# Shield.net
KiCad netlist of a schematic drawn in EAGLE
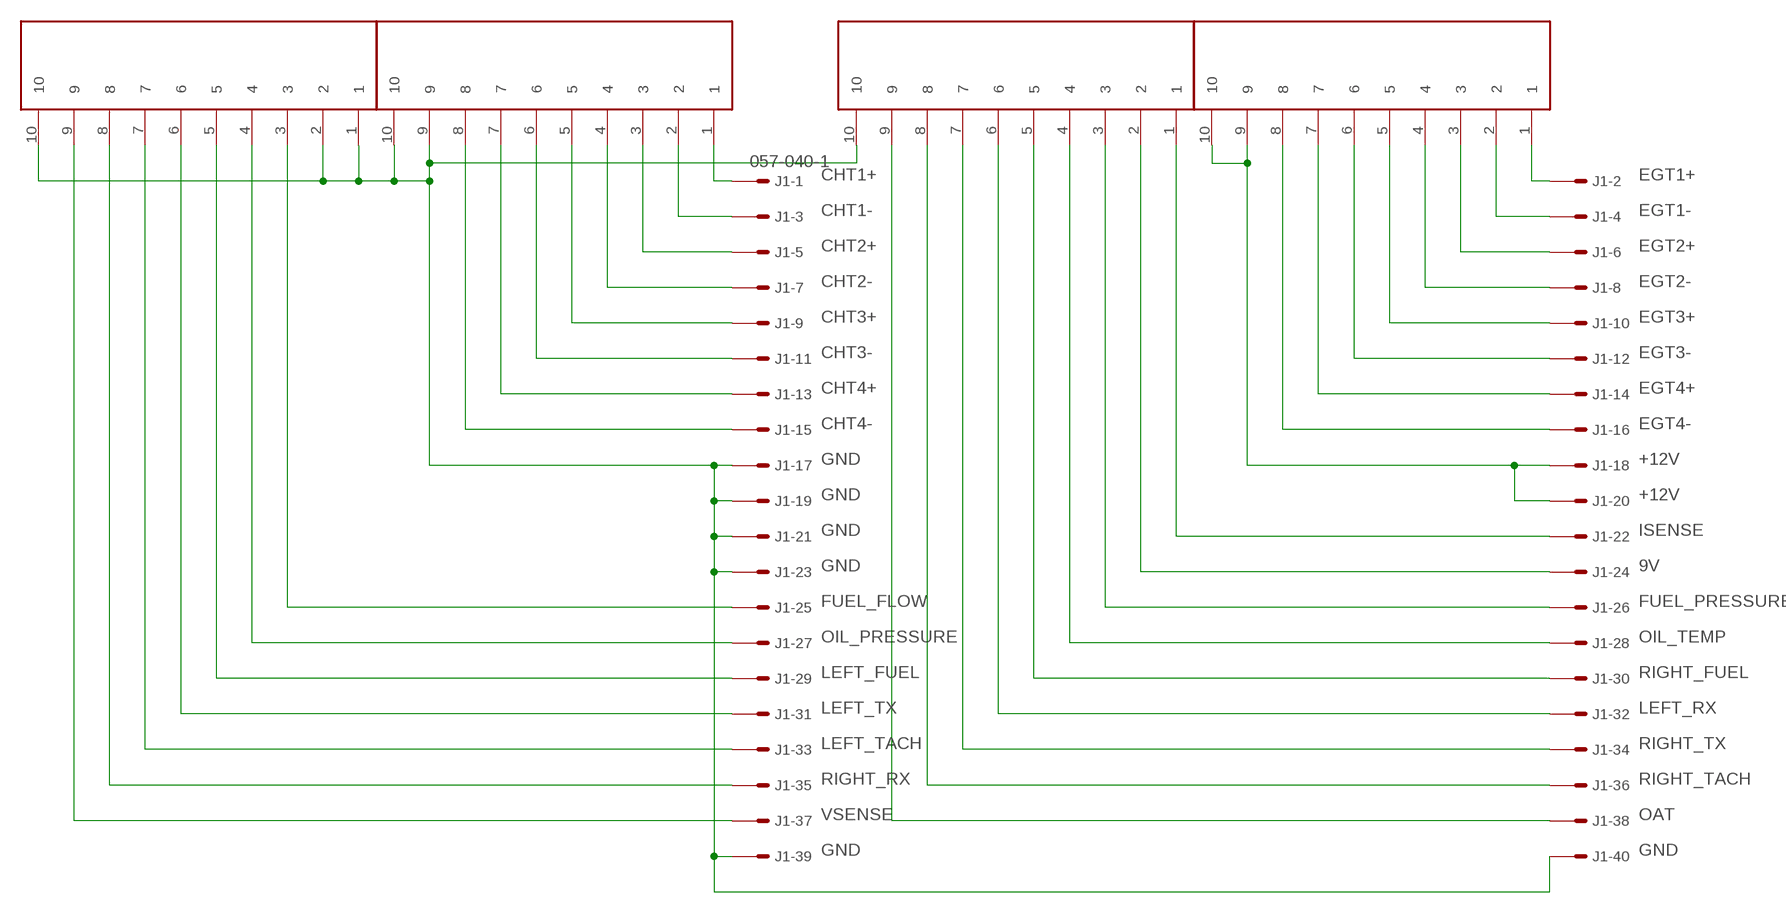
[diagram p0: schematic, sheet 1]

(export (version "E")
  (design (tool "Eeschema 10.0.6"))
  (components
    (comp (ref "J1")
      (value "057-040-1")
      (footprint "eagle-import:057-040-1")
      (fields (field (name "PARTNO") "SBH11-PBPC-D20-ST-BK"))
      (libsource (lib "eagle-import") (part "057-040-1"))
    )
    (comp (ref "TB1")
      (value "282847-10")
      (footprint "eagle-import:282847-10")
      (fields (field (name "PARTNO") "1-282847-0"))
      (libsource (lib "eagle-import") (part "282847-10"))
    )
    (comp (ref "TB2")
      (value "282847-10")
      (footprint "eagle-import:282847-10")
      (fields (field (name "PARTNO") "1-282847-0"))
      (libsource (lib "eagle-import") (part "282847-10"))
    )
    (comp (ref "TB3")
      (value "282847-10")
      (footprint "eagle-import:282847-10")
      (fields (field (name "PARTNO") "1-282847-0"))
      (libsource (lib "eagle-import") (part "282847-10"))
    )
    (comp (ref "TB4")
      (value "282847-10")
      (footprint "eagle-import:282847-10")
      (fields (field (name "PARTNO") "1-282847-0"))
      (libsource (lib "eagle-import") (part "282847-10"))
    )
  )
  (nets
    (net (code "1") (name "/+12V") (class "Default")
      (node (ref "J1") (pin "18") (pinfunction "S_18") (pintype "passive"))
      (node (ref "J1") (pin "20") (pinfunction "S_20") (pintype "passive"))
      (node (ref "TB4") (pin "10") (pinfunction "10_10") (pintype "bidirectional"))
      (node (ref "TB4") (pin "9") (pinfunction "9_9") (pintype "bidirectional"))
    )
    (net (code "2") (name "/9V") (class "Default")
      (node (ref "J1") (pin "24") (pinfunction "S_24") (pintype "passive"))
      (node (ref "TB3") (pin "2") (pinfunction "2_2") (pintype "bidirectional"))
    )
    (net (code "3") (name "/CHT1+") (class "Default")
      (node (ref "J1") (pin "1") (pinfunction "S_1") (pintype "passive"))
      (node (ref "TB2") (pin "1") (pinfunction "1_1") (pintype "bidirectional"))
    )
    (net (code "4") (name "/CHT1-") (class "Default")
      (node (ref "J1") (pin "3") (pinfunction "S_3") (pintype "passive"))
      (node (ref "TB2") (pin "2") (pinfunction "2_2") (pintype "bidirectional"))
    )
    (net (code "5") (name "/CHT2+") (class "Default")
      (node (ref "J1") (pin "5") (pinfunction "S_5") (pintype "passive"))
      (node (ref "TB2") (pin "3") (pinfunction "3_3") (pintype "bidirectional"))
    )
    (net (code "6") (name "/CHT2-") (class "Default")
      (node (ref "J1") (pin "7") (pinfunction "S_7") (pintype "passive"))
      (node (ref "TB2") (pin "4") (pinfunction "4_4") (pintype "bidirectional"))
    )
    (net (code "7") (name "/CHT3+") (class "Default")
      (node (ref "J1") (pin "9") (pinfunction "S_9") (pintype "passive"))
      (node (ref "TB2") (pin "5") (pinfunction "5_5") (pintype "bidirectional"))
    )
    (net (code "8") (name "/CHT3-") (class "Default")
      (node (ref "J1") (pin "11") (pinfunction "S_11") (pintype "passive"))
      (node (ref "TB2") (pin "6") (pinfunction "6_6") (pintype "bidirectional"))
    )
    (net (code "9") (name "/CHT4+") (class "Default")
      (node (ref "J1") (pin "13") (pinfunction "S_13") (pintype "passive"))
      (node (ref "TB2") (pin "7") (pinfunction "7_7") (pintype "bidirectional"))
    )
    (net (code "10") (name "/CHT4-") (class "Default")
      (node (ref "J1") (pin "15") (pinfunction "S_15") (pintype "passive"))
      (node (ref "TB2") (pin "8") (pinfunction "8_8") (pintype "bidirectional"))
    )
    (net (code "11") (name "/EGT1+") (class "Default")
      (node (ref "J1") (pin "2") (pinfunction "S_2") (pintype "passive"))
      (node (ref "TB4") (pin "1") (pinfunction "1_1") (pintype "bidirectional"))
    )
    (net (code "12") (name "/EGT1-") (class "Default")
      (node (ref "J1") (pin "4") (pinfunction "S_4") (pintype "passive"))
      (node (ref "TB4") (pin "2") (pinfunction "2_2") (pintype "bidirectional"))
    )
    (net (code "13") (name "/EGT2+") (class "Default")
      (node (ref "J1") (pin "6") (pinfunction "S_6") (pintype "passive"))
      (node (ref "TB4") (pin "3") (pinfunction "3_3") (pintype "bidirectional"))
    )
    (net (code "14") (name "/EGT2-") (class "Default")
      (node (ref "J1") (pin "8") (pinfunction "S_8") (pintype "passive"))
      (node (ref "TB4") (pin "4") (pinfunction "4_4") (pintype "bidirectional"))
    )
    (net (code "15") (name "/EGT3+") (class "Default")
      (node (ref "J1") (pin "10") (pinfunction "S_10") (pintype "passive"))
      (node (ref "TB4") (pin "5") (pinfunction "5_5") (pintype "bidirectional"))
    )
    (net (code "16") (name "/EGT3-") (class "Default")
      (node (ref "J1") (pin "12") (pinfunction "S_12") (pintype "passive"))
      (node (ref "TB4") (pin "6") (pinfunction "6_6") (pintype "bidirectional"))
    )
    (net (code "17") (name "/EGT4+") (class "Default")
      (node (ref "J1") (pin "14") (pinfunction "S_14") (pintype "passive"))
      (node (ref "TB4") (pin "7") (pinfunction "7_7") (pintype "bidirectional"))
    )
    (net (code "18") (name "/EGT4-") (class "Default")
      (node (ref "J1") (pin "16") (pinfunction "S_16") (pintype "passive"))
      (node (ref "TB4") (pin "8") (pinfunction "8_8") (pintype "bidirectional"))
    )
    (net (code "19") (name "/FUEL_FLOW") (class "Default")
      (node (ref "J1") (pin "25") (pinfunction "S_25") (pintype "passive"))
      (node (ref "TB1") (pin "3") (pinfunction "3_3") (pintype "bidirectional"))
    )
    (net (code "20") (name "/FUEL_PRESSURE") (class "Default")
      (node (ref "J1") (pin "26") (pinfunction "S_26") (pintype "passive"))
      (node (ref "TB3") (pin "3") (pinfunction "3_3") (pintype "bidirectional"))
    )
    (net (code "21") (name "/GND") (class "Default")
      (node (ref "J1") (pin "17") (pinfunction "S_17") (pintype "passive"))
      (node (ref "J1") (pin "19") (pinfunction "S_19") (pintype "passive"))
      (node (ref "J1") (pin "21") (pinfunction "S_21") (pintype "passive"))
      (node (ref "J1") (pin "23") (pinfunction "S_23") (pintype "passive"))
      (node (ref "J1") (pin "39") (pinfunction "S_39") (pintype "passive"))
      (node (ref "J1") (pin "40") (pinfunction "S_40") (pintype "passive"))
      (node (ref "TB1") (pin "1") (pinfunction "1_1") (pintype "bidirectional"))
      (node (ref "TB1") (pin "10") (pinfunction "10_10") (pintype "bidirectional"))
      (node (ref "TB1") (pin "2") (pinfunction "2_2") (pintype "bidirectional"))
      (node (ref "TB2") (pin "10") (pinfunction "10_10") (pintype "bidirectional"))
      (node (ref "TB2") (pin "9") (pinfunction "9_9") (pintype "bidirectional"))
      (node (ref "TB3") (pin "10") (pinfunction "10_10") (pintype "bidirectional"))
    )
    (net (code "22") (name "/ISENSE") (class "Default")
      (node (ref "J1") (pin "22") (pinfunction "S_22") (pintype "passive"))
      (node (ref "TB3") (pin "1") (pinfunction "1_1") (pintype "bidirectional"))
    )
    (net (code "23") (name "/LEFT_FUEL") (class "Default")
      (node (ref "J1") (pin "29") (pinfunction "S_29") (pintype "passive"))
      (node (ref "TB1") (pin "5") (pinfunction "5_5") (pintype "bidirectional"))
    )
    (net (code "24") (name "/LEFT_RX") (class "Default")
      (node (ref "J1") (pin "32") (pinfunction "S_32") (pintype "passive"))
      (node (ref "TB3") (pin "6") (pinfunction "6_6") (pintype "bidirectional"))
    )
    (net (code "25") (name "/LEFT_TACH") (class "Default")
      (node (ref "J1") (pin "33") (pinfunction "S_33") (pintype "passive"))
      (node (ref "TB1") (pin "7") (pinfunction "7_7") (pintype "bidirectional"))
    )
    (net (code "26") (name "/LEFT_TX") (class "Default")
      (node (ref "J1") (pin "31") (pinfunction "S_31") (pintype "passive"))
      (node (ref "TB1") (pin "6") (pinfunction "6_6") (pintype "bidirectional"))
    )
    (net (code "27") (name "/OAT") (class "Default")
      (node (ref "J1") (pin "38") (pinfunction "S_38") (pintype "passive"))
      (node (ref "TB3") (pin "9") (pinfunction "9_9") (pintype "bidirectional"))
    )
    (net (code "28") (name "/OIL_PRESSURE") (class "Default")
      (node (ref "J1") (pin "27") (pinfunction "S_27") (pintype "passive"))
      (node (ref "TB1") (pin "4") (pinfunction "4_4") (pintype "bidirectional"))
    )
    (net (code "29") (name "/OIL_TEMP") (class "Default")
      (node (ref "J1") (pin "28") (pinfunction "S_28") (pintype "passive"))
      (node (ref "TB3") (pin "4") (pinfunction "4_4") (pintype "bidirectional"))
    )
    (net (code "30") (name "/RIGHT_FUEL") (class "Default")
      (node (ref "J1") (pin "30") (pinfunction "S_30") (pintype "passive"))
      (node (ref "TB3") (pin "5") (pinfunction "5_5") (pintype "bidirectional"))
    )
    (net (code "31") (name "/RIGHT_RX") (class "Default")
      (node (ref "J1") (pin "35") (pinfunction "S_35") (pintype "passive"))
      (node (ref "TB1") (pin "8") (pinfunction "8_8") (pintype "bidirectional"))
    )
    (net (code "32") (name "/RIGHT_TACH") (class "Default")
      (node (ref "J1") (pin "36") (pinfunction "S_36") (pintype "passive"))
      (node (ref "TB3") (pin "8") (pinfunction "8_8") (pintype "bidirectional"))
    )
    (net (code "33") (name "/RIGHT_TX") (class "Default")
      (node (ref "J1") (pin "34") (pinfunction "S_34") (pintype "passive"))
      (node (ref "TB3") (pin "7") (pinfunction "7_7") (pintype "bidirectional"))
    )
    (net (code "34") (name "/VSENSE") (class "Default")
      (node (ref "J1") (pin "37") (pinfunction "S_37") (pintype "passive"))
      (node (ref "TB1") (pin "9") (pinfunction "9_9") (pintype "bidirectional"))
    )
  )
)
